# P04_MPU3.net
KiCad netlist of a schematic drawn in Altium Designer
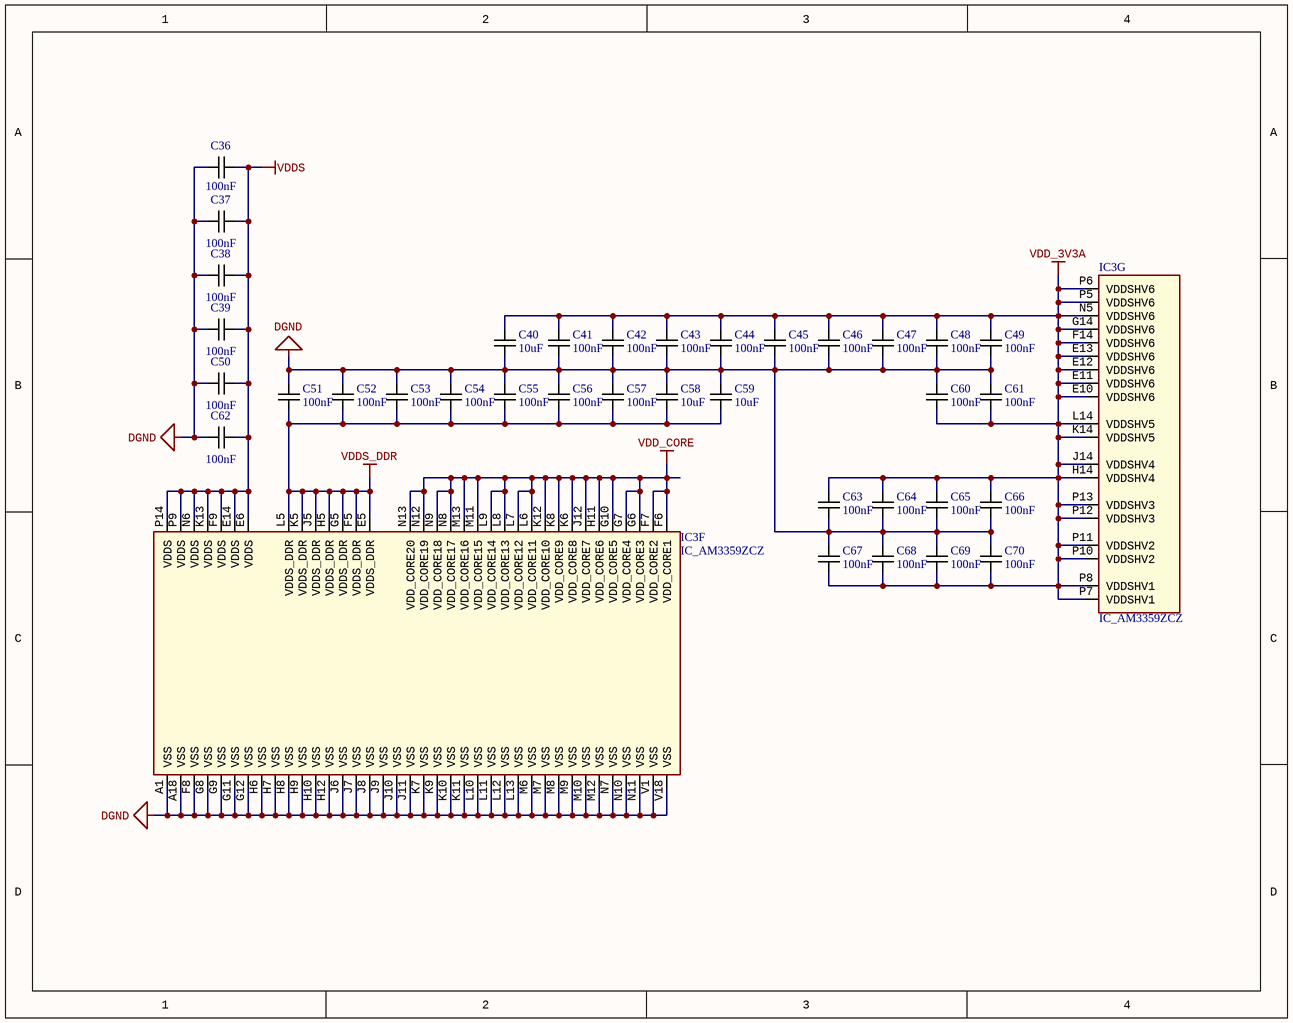
[diagram p0: P04_MPU3.SchDoc]

(export (version "E")
  (design (tool "Eeschema 10.0.6"))
  (components
    (comp (ref "C36")
      (value "C0402C104K4RACTU")
      (footprint "Orient:CAP0402")
      (description "MLCC 100nF 0402 SMD")
      (fields
        (field (name "MANUFACTURER") "KEMET")
        (field (name "CAPACITANCE") "100nF")
        (field (name "TOLERANCE") "10%")
      )
      (libsource (lib "Orient") (part "CAP_100nF"))
    )
    (comp (ref "C37")
      (value "C0402C104K4RACTU")
      (footprint "Orient:CAP0402")
      (description "MLCC 100nF 0402 SMD")
      (fields
        (field (name "MANUFACTURER") "KEMET")
        (field (name "CAPACITANCE") "100nF")
        (field (name "TOLERANCE") "10%")
      )
      (libsource (lib "Orient") (part "CAP_100nF"))
    )
    (comp (ref "C38")
      (value "C0402C104K4RACTU")
      (footprint "Orient:CAP0402")
      (description "MLCC 100nF 0402 SMD")
      (fields
        (field (name "MANUFACTURER") "KEMET")
        (field (name "CAPACITANCE") "100nF")
        (field (name "TOLERANCE") "10%")
      )
      (libsource (lib "Orient") (part "CAP_100nF"))
    )
    (comp (ref "C39")
      (value "C0402C104K4RACTU")
      (footprint "Orient:CAP0402")
      (description "MLCC 100nF 0402 SMD")
      (fields
        (field (name "MANUFACTURER") "KEMET")
        (field (name "CAPACITANCE") "100nF")
        (field (name "TOLERANCE") "10%")
      )
      (libsource (lib "Orient") (part "CAP_100nF"))
    )
    (comp (ref "C40")
      (value "C2012X6S1A106K085AC")
      (footprint "Orient:CAP0805")
      (description "MLCC 10uF 0805 SMD")
      (fields
        (field (name "MANUFACTURER") "TDK")
        (field (name "CAPACITANCE") "10uF")
        (field (name "TOLERANCE") "10%")
      )
      (libsource (lib "Orient") (part "CAP_10uF"))
    )
    (comp (ref "C41")
      (value "C0402C104K4RACTU")
      (footprint "Orient:CAP0402")
      (description "MLCC 100nF 0402 SMD")
      (fields
        (field (name "MANUFACTURER") "KEMET")
        (field (name "CAPACITANCE") "100nF")
        (field (name "TOLERANCE") "10%")
      )
      (libsource (lib "Orient") (part "CAP_100nF"))
    )
    (comp (ref "C42")
      (value "C0402C104K4RACTU")
      (footprint "Orient:CAP0402")
      (description "MLCC 100nF 0402 SMD")
      (fields
        (field (name "MANUFACTURER") "KEMET")
        (field (name "CAPACITANCE") "100nF")
        (field (name "TOLERANCE") "10%")
      )
      (libsource (lib "Orient") (part "CAP_100nF"))
    )
    (comp (ref "C43")
      (value "C0402C104K4RACTU")
      (footprint "Orient:CAP0402")
      (description "MLCC 100nF 0402 SMD")
      (fields
        (field (name "MANUFACTURER") "KEMET")
        (field (name "CAPACITANCE") "100nF")
        (field (name "TOLERANCE") "10%")
      )
      (libsource (lib "Orient") (part "CAP_100nF"))
    )
    (comp (ref "C44")
      (value "C0402C104K4RACTU")
      (footprint "Orient:CAP0402")
      (description "MLCC 100nF 0402 SMD")
      (fields
        (field (name "MANUFACTURER") "KEMET")
        (field (name "CAPACITANCE") "100nF")
        (field (name "TOLERANCE") "10%")
      )
      (libsource (lib "Orient") (part "CAP_100nF"))
    )
    (comp (ref "C45")
      (value "C0402C104K4RACTU")
      (footprint "Orient:CAP0402")
      (description "MLCC 100nF 0402 SMD")
      (fields
        (field (name "MANUFACTURER") "KEMET")
        (field (name "CAPACITANCE") "100nF")
        (field (name "TOLERANCE") "10%")
      )
      (libsource (lib "Orient") (part "CAP_100nF"))
    )
    (comp (ref "C46")
      (value "C0402C104K4RACTU")
      (footprint "Orient:CAP0402")
      (description "MLCC 100nF 0402 SMD")
      (fields
        (field (name "MANUFACTURER") "KEMET")
        (field (name "CAPACITANCE") "100nF")
        (field (name "TOLERANCE") "10%")
      )
      (libsource (lib "Orient") (part "CAP_100nF"))
    )
    (comp (ref "C47")
      (value "C0402C104K4RACTU")
      (footprint "Orient:CAP0402")
      (description "MLCC 100nF 0402 SMD")
      (fields
        (field (name "MANUFACTURER") "KEMET")
        (field (name "CAPACITANCE") "100nF")
        (field (name "TOLERANCE") "10%")
      )
      (libsource (lib "Orient") (part "CAP_100nF"))
    )
    (comp (ref "C48")
      (value "C0402C104K4RACTU")
      (footprint "Orient:CAP0402")
      (description "MLCC 100nF 0402 SMD")
      (fields
        (field (name "MANUFACTURER") "KEMET")
        (field (name "CAPACITANCE") "100nF")
        (field (name "TOLERANCE") "10%")
      )
      (libsource (lib "Orient") (part "CAP_100nF"))
    )
    (comp (ref "C49")
      (value "C0402C104K4RACTU")
      (footprint "Orient:CAP0402")
      (description "MLCC 100nF 0402 SMD")
      (fields
        (field (name "MANUFACTURER") "KEMET")
        (field (name "CAPACITANCE") "100nF")
        (field (name "TOLERANCE") "10%")
      )
      (libsource (lib "Orient") (part "CAP_100nF"))
    )
    (comp (ref "C50")
      (value "C0402C104K4RACTU")
      (footprint "Orient:CAP0402")
      (description "MLCC 100nF 0402 SMD")
      (fields
        (field (name "MANUFACTURER") "KEMET")
        (field (name "CAPACITANCE") "100nF")
        (field (name "TOLERANCE") "10%")
      )
      (libsource (lib "Orient") (part "CAP_100nF"))
    )
    (comp (ref "C51")
      (value "C0402C104K4RACTU")
      (footprint "Orient:CAP0402")
      (description "MLCC 100nF 0402 SMD")
      (fields
        (field (name "MANUFACTURER") "KEMET")
        (field (name "CAPACITANCE") "100nF")
        (field (name "TOLERANCE") "10%")
      )
      (libsource (lib "Orient") (part "CAP_100nF"))
    )
    (comp (ref "C52")
      (value "C0402C104K4RACTU")
      (footprint "Orient:CAP0402")
      (description "MLCC 100nF 0402 SMD")
      (fields
        (field (name "MANUFACTURER") "KEMET")
        (field (name "CAPACITANCE") "100nF")
        (field (name "TOLERANCE") "10%")
      )
      (libsource (lib "Orient") (part "CAP_100nF"))
    )
    (comp (ref "C53")
      (value "C0402C104K4RACTU")
      (footprint "Orient:CAP0402")
      (description "MLCC 100nF 0402 SMD")
      (fields
        (field (name "MANUFACTURER") "KEMET")
        (field (name "CAPACITANCE") "100nF")
        (field (name "TOLERANCE") "10%")
      )
      (libsource (lib "Orient") (part "CAP_100nF"))
    )
    (comp (ref "C54")
      (value "C0402C104K4RACTU")
      (footprint "Orient:CAP0402")
      (description "MLCC 100nF 0402 SMD")
      (fields
        (field (name "MANUFACTURER") "KEMET")
        (field (name "CAPACITANCE") "100nF")
        (field (name "TOLERANCE") "10%")
      )
      (libsource (lib "Orient") (part "CAP_100nF"))
    )
    (comp (ref "C55")
      (value "C0402C104K4RACTU")
      (footprint "Orient:CAP0402")
      (description "MLCC 100nF 0402 SMD")
      (fields
        (field (name "MANUFACTURER") "KEMET")
        (field (name "CAPACITANCE") "100nF")
        (field (name "TOLERANCE") "10%")
      )
      (libsource (lib "Orient") (part "CAP_100nF"))
    )
    (comp (ref "C56")
      (value "C0402C104K4RACTU")
      (footprint "Orient:CAP0402")
      (description "MLCC 100nF 0402 SMD")
      (fields
        (field (name "MANUFACTURER") "KEMET")
        (field (name "CAPACITANCE") "100nF")
        (field (name "TOLERANCE") "10%")
      )
      (libsource (lib "Orient") (part "CAP_100nF"))
    )
    (comp (ref "C57")
      (value "C0402C104K4RACTU")
      (footprint "Orient:CAP0402")
      (description "MLCC 100nF 0402 SMD")
      (fields
        (field (name "MANUFACTURER") "KEMET")
        (field (name "CAPACITANCE") "100nF")
        (field (name "TOLERANCE") "10%")
      )
      (libsource (lib "Orient") (part "CAP_100nF"))
    )
    (comp (ref "C58")
      (value "C2012X6S1A106K085AC")
      (footprint "Orient:CAP0805")
      (description "MLCC 10uF 0805 SMD")
      (fields
        (field (name "MANUFACTURER") "TDK")
        (field (name "CAPACITANCE") "10uF")
        (field (name "TOLERANCE") "10%")
      )
      (libsource (lib "Orient") (part "CAP_10uF"))
    )
    (comp (ref "C59")
      (value "C2012X6S1A106K085AC")
      (footprint "Orient:CAP0805")
      (description "MLCC 10uF 0805 SMD")
      (fields
        (field (name "MANUFACTURER") "TDK")
        (field (name "CAPACITANCE") "10uF")
        (field (name "TOLERANCE") "10%")
      )
      (libsource (lib "Orient") (part "CAP_10uF"))
    )
    (comp (ref "C60")
      (value "C0402C104K4RACTU")
      (footprint "Orient:CAP0402")
      (description "MLCC 100nF 0402 SMD")
      (fields
        (field (name "MANUFACTURER") "KEMET")
        (field (name "CAPACITANCE") "100nF")
        (field (name "TOLERANCE") "10%")
      )
      (libsource (lib "Orient") (part "CAP_100nF"))
    )
    (comp (ref "C61")
      (value "C0402C104K4RACTU")
      (footprint "Orient:CAP0402")
      (description "MLCC 100nF 0402 SMD")
      (fields
        (field (name "MANUFACTURER") "KEMET")
        (field (name "CAPACITANCE") "100nF")
        (field (name "TOLERANCE") "10%")
      )
      (libsource (lib "Orient") (part "CAP_100nF"))
    )
    (comp (ref "C62")
      (value "C0402C104K4RACTU")
      (footprint "Orient:CAP0402")
      (description "MLCC 100nF 0402 SMD")
      (fields
        (field (name "MANUFACTURER") "KEMET")
        (field (name "CAPACITANCE") "100nF")
        (field (name "TOLERANCE") "10%")
      )
      (libsource (lib "Orient") (part "CAP_100nF"))
    )
    (comp (ref "C63")
      (value "C0402C104K4RACTU")
      (footprint "Orient:CAP0402")
      (description "MLCC 100nF 0402 SMD")
      (fields
        (field (name "MANUFACTURER") "KEMET")
        (field (name "CAPACITANCE") "100nF")
        (field (name "TOLERANCE") "10%")
      )
      (libsource (lib "Orient") (part "CAP_100nF"))
    )
    (comp (ref "C64")
      (value "C0402C104K4RACTU")
      (footprint "Orient:CAP0402")
      (description "MLCC 100nF 0402 SMD")
      (fields
        (field (name "MANUFACTURER") "KEMET")
        (field (name "CAPACITANCE") "100nF")
        (field (name "TOLERANCE") "10%")
      )
      (libsource (lib "Orient") (part "CAP_100nF"))
    )
    (comp (ref "C65")
      (value "C0402C104K4RACTU")
      (footprint "Orient:CAP0402")
      (description "MLCC 100nF 0402 SMD")
      (fields
        (field (name "MANUFACTURER") "KEMET")
        (field (name "CAPACITANCE") "100nF")
        (field (name "TOLERANCE") "10%")
      )
      (libsource (lib "Orient") (part "CAP_100nF"))
    )
    (comp (ref "C66")
      (value "C0402C104K4RACTU")
      (footprint "Orient:CAP0402")
      (description "MLCC 100nF 0402 SMD")
      (fields
        (field (name "MANUFACTURER") "KEMET")
        (field (name "CAPACITANCE") "100nF")
        (field (name "TOLERANCE") "10%")
      )
      (libsource (lib "Orient") (part "CAP_100nF"))
    )
    (comp (ref "C67")
      (value "C0402C104K4RACTU")
      (footprint "Orient:CAP0402")
      (description "MLCC 100nF 0402 SMD")
      (fields
        (field (name "MANUFACTURER") "KEMET")
        (field (name "CAPACITANCE") "100nF")
        (field (name "TOLERANCE") "10%")
      )
      (libsource (lib "Orient") (part "CAP_100nF"))
    )
    (comp (ref "C68")
      (value "C0402C104K4RACTU")
      (footprint "Orient:CAP0402")
      (description "MLCC 100nF 0402 SMD")
      (fields
        (field (name "MANUFACTURER") "KEMET")
        (field (name "CAPACITANCE") "100nF")
        (field (name "TOLERANCE") "10%")
      )
      (libsource (lib "Orient") (part "CAP_100nF"))
    )
    (comp (ref "C69")
      (value "C0402C104K4RACTU")
      (footprint "Orient:CAP0402")
      (description "MLCC 100nF 0402 SMD")
      (fields
        (field (name "MANUFACTURER") "KEMET")
        (field (name "CAPACITANCE") "100nF")
        (field (name "TOLERANCE") "10%")
      )
      (libsource (lib "Orient") (part "CAP_100nF"))
    )
    (comp (ref "C70")
      (value "C0402C104K4RACTU")
      (footprint "Orient:CAP0402")
      (description "MLCC 100nF 0402 SMD")
      (fields
        (field (name "MANUFACTURER") "KEMET")
        (field (name "CAPACITANCE") "100nF")
        (field (name "TOLERANCE") "10%")
      )
      (libsource (lib "Orient") (part "CAP_100nF"))
    )
    (comp (ref "IC3")
      (value "IC_AM3359ZCZ")
      (footprint "Orient:BGA-324")
      (description "SubArctic Cortex A8 Processor 18x18")
      (fields
        (field (name "MANUFACTURER") "Texas Instruments")
        (field (name "MANUFACTURER PART NUMBER") "XAM3359ZCZ")
      )
      (libsource (lib "Orient") (part "IC_AM335X_ZCE_1"))
    )
  )
  (nets
    (net (code "1") (name "DGND") (class "Default")
      (node (ref "C36") (pin "2") (pintype "passive"))
      (node (ref "C37") (pin "2") (pintype "passive"))
      (node (ref "C38") (pin "2") (pintype "passive"))
      (node (ref "C39") (pin "2") (pintype "passive"))
      (node (ref "C40") (pin "2") (pintype "passive"))
      (node (ref "C41") (pin "1") (pintype "passive"))
      (node (ref "C42") (pin "1") (pintype "passive"))
      (node (ref "C43") (pin "1") (pintype "passive"))
      (node (ref "C44") (pin "1") (pintype "passive"))
      (node (ref "C45") (pin "1") (pintype "passive"))
      (node (ref "C46") (pin "1") (pintype "passive"))
      (node (ref "C47") (pin "1") (pintype "passive"))
      (node (ref "C48") (pin "1") (pintype "passive"))
      (node (ref "C49") (pin "1") (pintype "passive"))
      (node (ref "C50") (pin "2") (pintype "passive"))
      (node (ref "C51") (pin "2") (pintype "passive"))
      (node (ref "C52") (pin "2") (pintype "passive"))
      (node (ref "C53") (pin "2") (pintype "passive"))
      (node (ref "C54") (pin "2") (pintype "passive"))
      (node (ref "C55") (pin "2") (pintype "passive"))
      (node (ref "C56") (pin "2") (pintype "passive"))
      (node (ref "C57") (pin "2") (pintype "passive"))
      (node (ref "C58") (pin "1") (pintype "passive"))
      (node (ref "C59") (pin "1") (pintype "passive"))
      (node (ref "C60") (pin "2") (pintype "passive"))
      (node (ref "C61") (pin "2") (pintype "passive"))
      (node (ref "C62") (pin "2") (pintype "passive"))
      (node (ref "C63") (pin "1") (pintype "passive"))
      (node (ref "C64") (pin "1") (pintype "passive"))
      (node (ref "C65") (pin "1") (pintype "passive"))
      (node (ref "C66") (pin "1") (pintype "passive"))
      (node (ref "C67") (pin "2") (pintype "passive"))
      (node (ref "C68") (pin "2") (pintype "passive"))
      (node (ref "C69") (pin "2") (pintype "passive"))
      (node (ref "C70") (pin "2") (pintype "passive"))
      (node (ref "IC3") (pin "A1") (pinfunction "VSS_A1") (pintype "power_in"))
      (node (ref "IC3") (pin "A18") (pinfunction "VSS_A18") (pintype "power_in"))
      (node (ref "IC3") (pin "F8") (pinfunction "VSS_F8") (pintype "power_in"))
      (node (ref "IC3") (pin "G11") (pinfunction "VSS_G11") (pintype "power_in"))
      (node (ref "IC3") (pin "G12") (pinfunction "VSS_G12") (pintype "power_in"))
      (node (ref "IC3") (pin "G8") (pinfunction "VSS_G8") (pintype "power_in"))
      (node (ref "IC3") (pin "G9") (pinfunction "VSS_G9") (pintype "power_in"))
      (node (ref "IC3") (pin "H10") (pinfunction "VSS_H10") (pintype "power_in"))
      (node (ref "IC3") (pin "H12") (pinfunction "VSS_H12") (pintype "power_in"))
      (node (ref "IC3") (pin "H6") (pinfunction "VSS_H6") (pintype "power_in"))
      (node (ref "IC3") (pin "H7") (pinfunction "VSS_H7") (pintype "power_in"))
      (node (ref "IC3") (pin "H8") (pinfunction "VSS_H8") (pintype "power_in"))
      (node (ref "IC3") (pin "H9") (pinfunction "VSS_H9") (pintype "power_in"))
      (node (ref "IC3") (pin "J10") (pinfunction "VSS_J10") (pintype "power_in"))
      (node (ref "IC3") (pin "J11") (pinfunction "VSS_J11") (pintype "power_in"))
      (node (ref "IC3") (pin "J6") (pinfunction "VSS_J6") (pintype "power_in"))
      (node (ref "IC3") (pin "J7") (pinfunction "VSS_J7") (pintype "power_in"))
      (node (ref "IC3") (pin "J8") (pinfunction "VSS_J8") (pintype "power_in"))
      (node (ref "IC3") (pin "J9") (pinfunction "VSS_J9") (pintype "power_in"))
      (node (ref "IC3") (pin "K10") (pinfunction "VSS_K10") (pintype "power_in"))
      (node (ref "IC3") (pin "K11") (pinfunction "VSS_K11") (pintype "power_in"))
      (node (ref "IC3") (pin "K7") (pinfunction "VSS_K7") (pintype "power_in"))
      (node (ref "IC3") (pin "K9") (pinfunction "VSS_K9") (pintype "power_in"))
      (node (ref "IC3") (pin "L10") (pinfunction "VSS_L10") (pintype "power_in"))
      (node (ref "IC3") (pin "L11") (pinfunction "VSS_L11") (pintype "power_in"))
      (node (ref "IC3") (pin "L12") (pinfunction "VSS_L12") (pintype "power_in"))
      (node (ref "IC3") (pin "L13") (pinfunction "VSS_L13") (pintype "power_in"))
      (node (ref "IC3") (pin "M10") (pinfunction "VSS_M10") (pintype "power_in"))
      (node (ref "IC3") (pin "M12") (pinfunction "VSS_M12") (pintype "power_in"))
      (node (ref "IC3") (pin "M6") (pinfunction "VSS_M6") (pintype "power_in"))
      (node (ref "IC3") (pin "M7") (pinfunction "VSS_M7") (pintype "power_in"))
      (node (ref "IC3") (pin "M8") (pinfunction "VSS_M8") (pintype "power_in"))
      (node (ref "IC3") (pin "M9") (pinfunction "VSS_M9") (pintype "power_in"))
      (node (ref "IC3") (pin "N10") (pinfunction "VSS_N10") (pintype "power_in"))
      (node (ref "IC3") (pin "N11") (pinfunction "VSS_N11") (pintype "power_in"))
      (node (ref "IC3") (pin "N7") (pinfunction "VSS_N7") (pintype "power_in"))
      (node (ref "IC3") (pin "V1") (pinfunction "VSS_V1") (pintype "power_in"))
      (node (ref "IC3") (pin "V18") (pinfunction "VSS_V18") (pintype "power_in"))
    )
    (net (code "2") (name "VDDS") (class "Default")
      (node (ref "C36") (pin "1") (pintype "passive"))
      (node (ref "C37") (pin "1") (pintype "passive"))
      (node (ref "C38") (pin "1") (pintype "passive"))
      (node (ref "C39") (pin "1") (pintype "passive"))
      (node (ref "C50") (pin "1") (pintype "passive"))
      (node (ref "C62") (pin "1") (pintype "passive"))
      (node (ref "IC3") (pin "E14") (pinfunction "VDDS_E14") (pintype "power_in"))
      (node (ref "IC3") (pin "E6") (pinfunction "VDDS_E6") (pintype "power_in"))
      (node (ref "IC3") (pin "F9") (pinfunction "VDDS_F9") (pintype "power_in"))
      (node (ref "IC3") (pin "K13") (pinfunction "VDDS_K13") (pintype "power_in"))
      (node (ref "IC3") (pin "N6") (pinfunction "VDDS_N6") (pintype "power_in"))
      (node (ref "IC3") (pin "P14") (pinfunction "VDDS_P14") (pintype "power_in"))
      (node (ref "IC3") (pin "P9") (pinfunction "VDDS_P9") (pintype "power_in"))
    )
    (net (code "3") (name "VDDS_DDR") (class "Default")
      (node (ref "C51") (pin "1") (pintype "passive"))
      (node (ref "C52") (pin "1") (pintype "passive"))
      (node (ref "C53") (pin "1") (pintype "passive"))
      (node (ref "C54") (pin "1") (pintype "passive"))
      (node (ref "C55") (pin "1") (pintype "passive"))
      (node (ref "C56") (pin "1") (pintype "passive"))
      (node (ref "C57") (pin "1") (pintype "passive"))
      (node (ref "C58") (pin "2") (pintype "passive"))
      (node (ref "C59") (pin "2") (pintype "passive"))
      (node (ref "IC3") (pin "E5") (pinfunction "VDDS_DDR_E5") (pintype "power_in"))
      (node (ref "IC3") (pin "F5") (pinfunction "VDDS_DDR_F5") (pintype "power_in"))
      (node (ref "IC3") (pin "G5") (pinfunction "VDDS_DDR_G5") (pintype "power_in"))
      (node (ref "IC3") (pin "H5") (pinfunction "VDDS_DDR_H5") (pintype "power_in"))
      (node (ref "IC3") (pin "J5") (pinfunction "VDDS_DDR_J5") (pintype "power_in"))
      (node (ref "IC3") (pin "K5") (pinfunction "VDDS_DDR_K5") (pintype "power_in"))
      (node (ref "IC3") (pin "L5") (pinfunction "VDDS_DDR_L5") (pintype "power_in"))
    )
    (net (code "4") (name "VDD_3V3A") (class "Default")
      (node (ref "C40") (pin "1") (pintype "passive"))
      (node (ref "C41") (pin "2") (pintype "passive"))
      (node (ref "C42") (pin "2") (pintype "passive"))
      (node (ref "C43") (pin "2") (pintype "passive"))
      (node (ref "C44") (pin "2") (pintype "passive"))
      (node (ref "C45") (pin "2") (pintype "passive"))
      (node (ref "C46") (pin "2") (pintype "passive"))
      (node (ref "C47") (pin "2") (pintype "passive"))
      (node (ref "C48") (pin "2") (pintype "passive"))
      (node (ref "C49") (pin "2") (pintype "passive"))
      (node (ref "C60") (pin "1") (pintype "passive"))
      (node (ref "C61") (pin "1") (pintype "passive"))
      (node (ref "C63") (pin "2") (pintype "passive"))
      (node (ref "C64") (pin "2") (pintype "passive"))
      (node (ref "C65") (pin "2") (pintype "passive"))
      (node (ref "C66") (pin "2") (pintype "passive"))
      (node (ref "C67") (pin "1") (pintype "passive"))
      (node (ref "C68") (pin "1") (pintype "passive"))
      (node (ref "C69") (pin "1") (pintype "passive"))
      (node (ref "C70") (pin "1") (pintype "passive"))
      (node (ref "IC3") (pin "E10") (pinfunction "VDDSHV6_E10") (pintype "power_in"))
      (node (ref "IC3") (pin "E11") (pinfunction "VDDSHV6_E11") (pintype "power_in"))
      (node (ref "IC3") (pin "E12") (pinfunction "VDDSHV6_E12") (pintype "power_in"))
      (node (ref "IC3") (pin "E13") (pinfunction "VDDSHV6_E13") (pintype "power_in"))
      (node (ref "IC3") (pin "F14") (pinfunction "VDDSHV6_F14") (pintype "power_in"))
      (node (ref "IC3") (pin "G14") (pinfunction "VDDSHV6_G14") (pintype "power_in"))
      (node (ref "IC3") (pin "H14") (pinfunction "VDDSHV4_H14") (pintype "power_in"))
      (node (ref "IC3") (pin "J14") (pinfunction "VDDSHV4_J14") (pintype "power_in"))
      (node (ref "IC3") (pin "K14") (pinfunction "VDDSHV5_K14") (pintype "power_in"))
      (node (ref "IC3") (pin "L14") (pinfunction "VDDSHV5_L14") (pintype "power_in"))
      (node (ref "IC3") (pin "N5") (pinfunction "VDDSHV6_N5") (pintype "power_in"))
      (node (ref "IC3") (pin "P10") (pinfunction "VDDSHV2_P10") (pintype "power_in"))
      (node (ref "IC3") (pin "P11") (pinfunction "VDDSHV2_P11") (pintype "power_in"))
      (node (ref "IC3") (pin "P12") (pinfunction "VDDSHV3_P12") (pintype "power_in"))
      (node (ref "IC3") (pin "P13") (pinfunction "VDDSHV3_P13") (pintype "power_in"))
      (node (ref "IC3") (pin "P5") (pinfunction "VDDSHV6_P5") (pintype "power_in"))
      (node (ref "IC3") (pin "P6") (pinfunction "VDDSHV6_P6") (pintype "power_in"))
      (node (ref "IC3") (pin "P7") (pinfunction "VDDSHV1_P7") (pintype "power_in"))
      (node (ref "IC3") (pin "P8") (pinfunction "VDDSHV1_P8") (pintype "power_in"))
    )
    (net (code "5") (name "VDD_CORE") (class "Default")
      (node (ref "IC3") (pin "F6") (pinfunction "VDD_CORE1_F6") (pintype "power_in"))
      (node (ref "IC3") (pin "F7") (pinfunction "VDD_CORE2_F7") (pintype "power_in"))
      (node (ref "IC3") (pin "G10") (pinfunction "VDD_CORE5_G10") (pintype "power_in"))
      (node (ref "IC3") (pin "G6") (pinfunction "VDD_CORE3_G6") (pintype "power_in"))
      (node (ref "IC3") (pin "G7") (pinfunction "VDD_CORE4_G7") (pintype "power_in"))
      (node (ref "IC3") (pin "H11") (pinfunction "VDD_CORE6_H11") (pintype "power_in"))
      (node (ref "IC3") (pin "J12") (pinfunction "VDD_CORE7_J12") (pintype "power_in"))
      (node (ref "IC3") (pin "K12") (pinfunction "VDD_CORE10_K12") (pintype "power_in"))
      (node (ref "IC3") (pin "K6") (pinfunction "VDD_CORE8_K6") (pintype "power_in"))
      (node (ref "IC3") (pin "K8") (pinfunction "VDD_CORE9_K8") (pintype "power_in"))
      (node (ref "IC3") (pin "L6") (pinfunction "VDD_CORE11_L6") (pintype "power_in"))
      (node (ref "IC3") (pin "L7") (pinfunction "VDD_CORE12_L7") (pintype "power_in"))
      (node (ref "IC3") (pin "L8") (pinfunction "VDD_CORE13_L8") (pintype "power_in"))
      (node (ref "IC3") (pin "L9") (pinfunction "VDD_CORE14_L9") (pintype "power_in"))
      (node (ref "IC3") (pin "M11") (pinfunction "VDD_CORE15_M11") (pintype "power_in"))
      (node (ref "IC3") (pin "M13") (pinfunction "VDD_CORE16_M13") (pintype "power_in"))
      (node (ref "IC3") (pin "N12") (pinfunction "VDD_CORE19_N12") (pintype "power_in"))
      (node (ref "IC3") (pin "N13") (pinfunction "VDD_CORE20_N13") (pintype "power_in"))
      (node (ref "IC3") (pin "N8") (pinfunction "VDD_CORE17_N8") (pintype "power_in"))
      (node (ref "IC3") (pin "N9") (pinfunction "VDD_CORE18_N9") (pintype "power_in"))
    )
  )
)
